# board.net
KiCad netlist of a schematic drawn in EAGLE
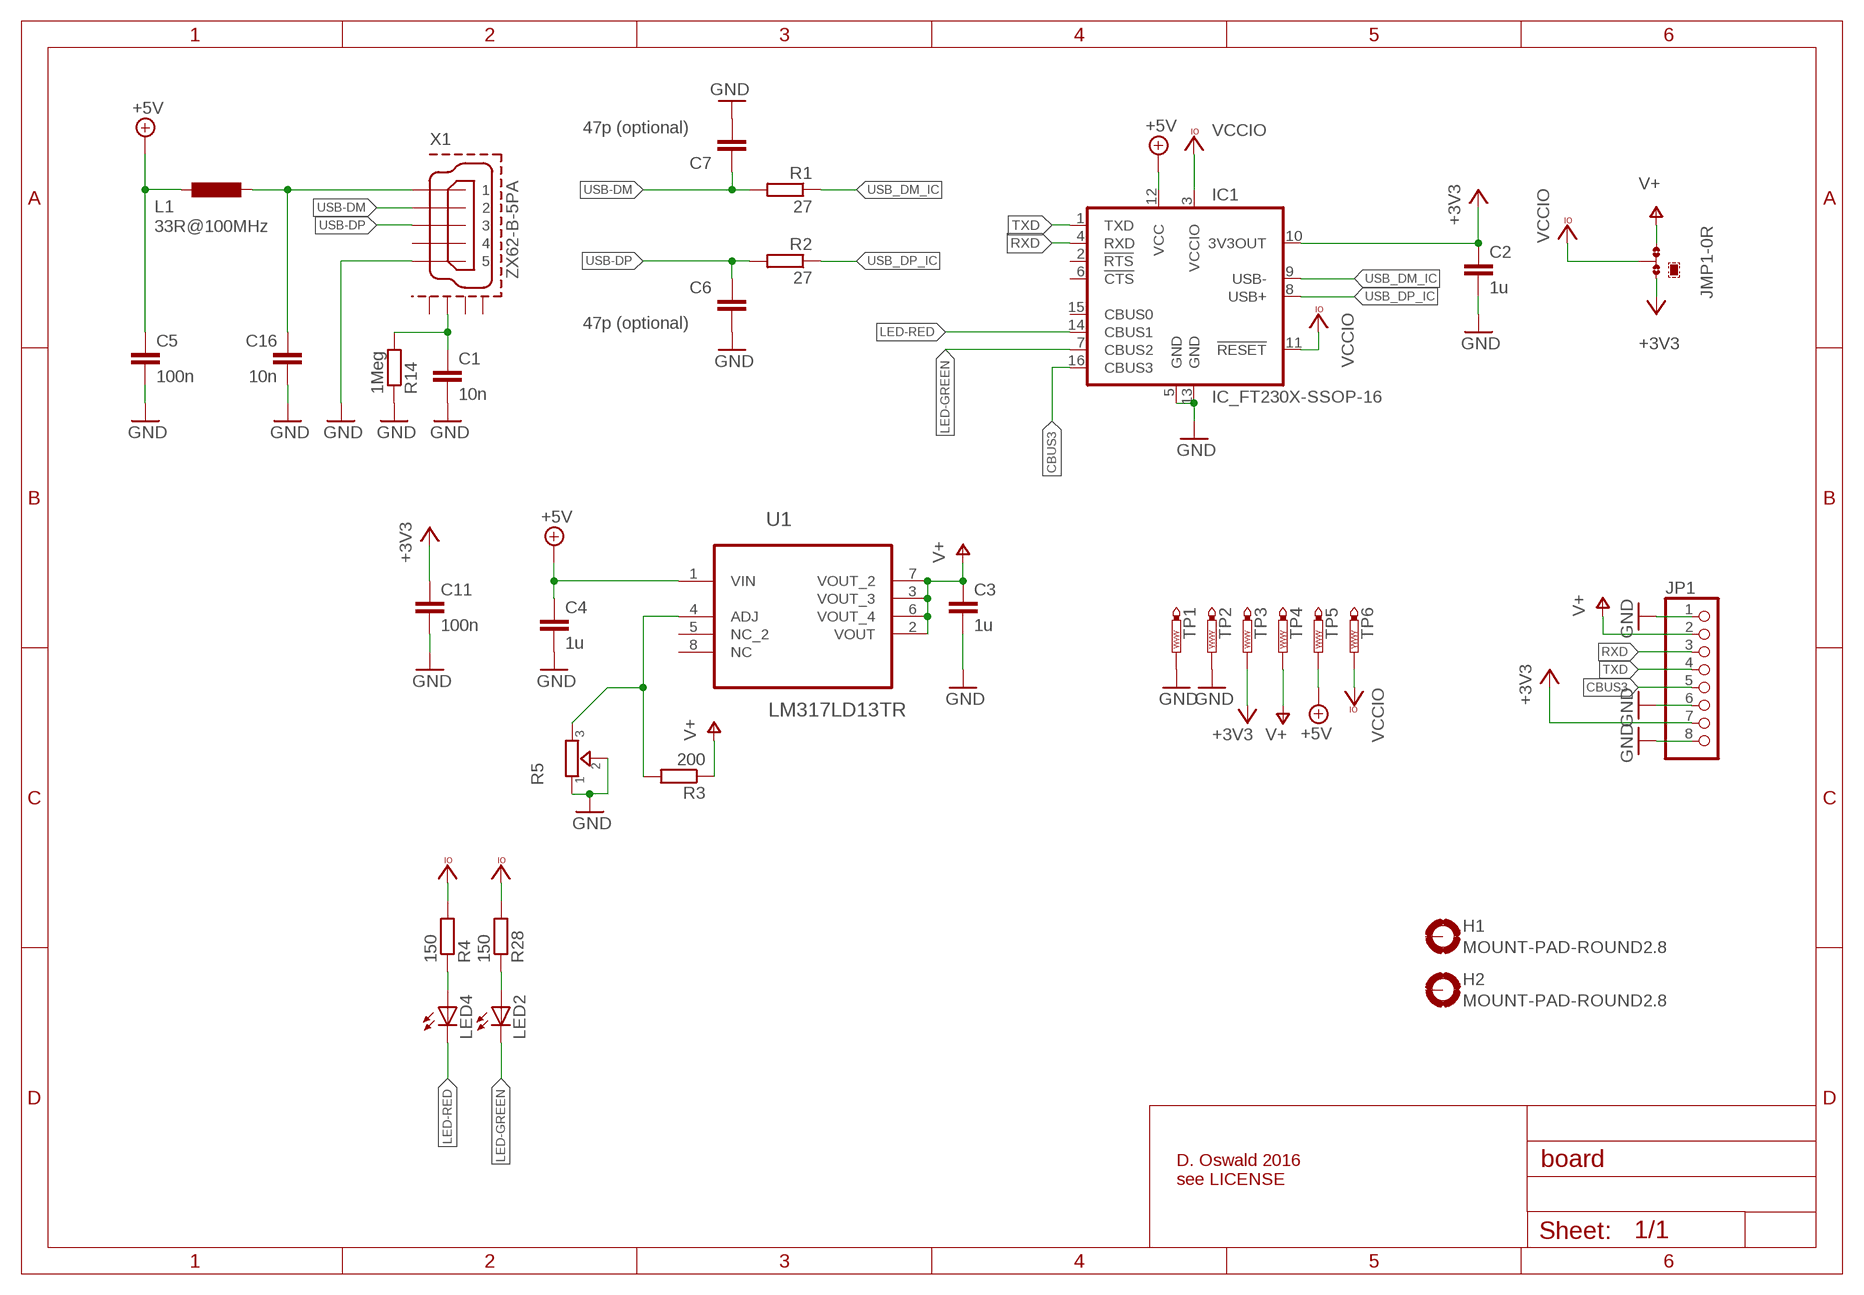
[diagram p0: schematic, sheet 1]

(export (version "E")
  (design (tool "Eeschema 10.0.6"))
  (components
    (comp (ref "C1")
      (value "10n")
      (footprint "eagle-import:C0603K")
      (libsource (lib "eagle-import") (part "C-EUC0603K"))
    )
    (comp (ref "C2")
      (value "1u")
      (footprint "eagle-import:C0805K")
      (libsource (lib "eagle-import") (part "C-EUC0805K"))
    )
    (comp (ref "C3")
      (value "1u")
      (footprint "eagle-import:C0805K")
      (libsource (lib "eagle-import") (part "C-EUC0805K"))
    )
    (comp (ref "C4")
      (value "1u")
      (footprint "eagle-import:C0805K")
      (libsource (lib "eagle-import") (part "C-EUC0805K"))
    )
    (comp (ref "C5")
      (value "100n")
      (footprint "eagle-import:C0603K")
      (libsource (lib "eagle-import") (part "C-EUC0603K"))
    )
    (comp (ref "C6")
      (value "47p (optional)")
      (footprint "eagle-import:C0603K")
      (libsource (lib "eagle-import") (part "C-EUC0603K"))
    )
    (comp (ref "C7")
      (value "47p (optional)")
      (footprint "eagle-import:C0603K")
      (libsource (lib "eagle-import") (part "C-EUC0603K"))
    )
    (comp (ref "C11")
      (value "100n")
      (footprint "eagle-import:C0603K")
      (libsource (lib "eagle-import") (part "C-EUC0603K"))
    )
    (comp (ref "C16")
      (value "10n")
      (footprint "eagle-import:C0603K")
      (libsource (lib "eagle-import") (part "C-EUC0603K"))
    )
    (comp (ref "H1")
      (value "MOUNT-PAD-ROUND2.8")
      (footprint "eagle-import:2,8-PAD")
      (libsource (lib "eagle-import") (part "MOUNT-PAD-ROUND2.8"))
    )
    (comp (ref "H2")
      (value "MOUNT-PAD-ROUND2.8")
      (footprint "eagle-import:2,8-PAD")
      (libsource (lib "eagle-import") (part "MOUNT-PAD-ROUND2.8"))
    )
    (comp (ref "IC1")
      (value "IC_FT230X-SSOP-16")
      (footprint "eagle-import:SSOP-16-FTDI")
      (libsource (lib "eagle-import") (part "IC_FT230X-SSOP-16"))
    )
    (comp (ref "JMP1")
      (value "0R-JUMPA")
      (footprint "eagle-import:A0R-JMP")
      (libsource (lib "eagle-import") (part "0R-JUMPA"))
    )
    (comp (ref "JP1")
      (value "PINHD-1X8/90")
      (footprint "eagle-import:1X08_90")
      (libsource (lib "eagle-import") (part "PINHD-1X8/90"))
    )
    (comp (ref "L1")
      (value "33R@100MHz")
      (footprint "eagle-import:L2012C")
      (libsource (lib "eagle-import") (part "L-EUL2012C"))
    )
    (comp (ref "LED2")
      (value "LEDCHIPLED_0805")
      (footprint "eagle-import:CHIPLED_0805")
      (libsource (lib "eagle-import") (part "LEDCHIPLED_0805"))
    )
    (comp (ref "LED4")
      (value "LEDCHIPLED_0805")
      (footprint "eagle-import:CHIPLED_0805")
      (libsource (lib "eagle-import") (part "LEDCHIPLED_0805"))
    )
    (comp (ref "R1")
      (value "27")
      (footprint "eagle-import:R0603")
      (libsource (lib "eagle-import") (part "R-EU_R0603"))
    )
    (comp (ref "R2")
      (value "27")
      (footprint "eagle-import:R0603")
      (libsource (lib "eagle-import") (part "R-EU_R0603"))
    )
    (comp (ref "R3")
      (value "200")
      (footprint "eagle-import:R0805")
      (libsource (lib "eagle-import") (part "R-EU_R0805"))
    )
    (comp (ref "R4")
      (value "150")
      (footprint "eagle-import:R0603")
      (libsource (lib "eagle-import") (part "R-EU_R0603"))
    )
    (comp (ref "R5")
      (value "TRIMMER-3314G")
      (footprint "eagle-import:TRIMMER_3314G")
      (libsource (lib "eagle-import") (part "TRIMMER-3314G"))
    )
    (comp (ref "R14")
      (value "1Meg")
      (footprint "eagle-import:R0603")
      (libsource (lib "eagle-import") (part "R-EU_R0603"))
    )
    (comp (ref "R28")
      (value "150")
      (footprint "eagle-import:R0603")
      (libsource (lib "eagle-import") (part "R-EU_R0603"))
    )
    (comp (ref "TP1")
      (value "PTR1B1,27")
      (footprint "eagle-import:B1,27")
      (libsource (lib "eagle-import") (part "PTR1B1,27"))
    )
    (comp (ref "TP2")
      (value "PTR1B1,27")
      (footprint "eagle-import:B1,27")
      (libsource (lib "eagle-import") (part "PTR1B1,27"))
    )
    (comp (ref "TP3")
      (value "PTR1B1,27")
      (footprint "eagle-import:B1,27")
      (libsource (lib "eagle-import") (part "PTR1B1,27"))
    )
    (comp (ref "TP4")
      (value "PTR1B1,27")
      (footprint "eagle-import:B1,27")
      (libsource (lib "eagle-import") (part "PTR1B1,27"))
    )
    (comp (ref "TP5")
      (value "PTR1B1,27")
      (footprint "eagle-import:B1,27")
      (libsource (lib "eagle-import") (part "PTR1B1,27"))
    )
    (comp (ref "TP6")
      (value "PTR1B1,27")
      (footprint "eagle-import:B1,27")
      (libsource (lib "eagle-import") (part "PTR1B1,27"))
    )
    (comp (ref "U1")
      (value "LM317LD13TR")
      (footprint "eagle-import:SOIC127P600X175-8N")
      (libsource (lib "eagle-import") (part "LM317LD13TR"))
    )
    (comp (ref "X1")
      (value "ZX62-B-5PA")
      (footprint "eagle-import:ZX62-B-5PA-LONG")
      (libsource (lib "eagle-import") (part "ZX62-B-5PA-LONG"))
    )
  )
  (nets
    (net (code "1") (name "+3V3") (class "Default")
      (node (ref "C11") (pin "1") (pinfunction "1_1") (pintype "passive"))
      (node (ref "C2") (pin "1") (pinfunction "1_1") (pintype "passive"))
      (node (ref "IC1") (pin "10") (pinfunction "3V3OUT_10") (pintype "power_in"))
      (node (ref "JMP1") (pin "1") (pinfunction "1_1") (pintype "passive"))
      (node (ref "JP1") (pin "7") (pinfunction "7_7") (pintype "passive"))
      (node (ref "TP3") (pin "TP") (pinfunction "TP_TP") (pintype "input"))
    )
    (net (code "2") (name "+5V") (class "Default")
      (node (ref "C4") (pin "1") (pinfunction "1_1") (pintype "passive"))
      (node (ref "C5") (pin "1") (pinfunction "1_1") (pintype "passive"))
      (node (ref "IC1") (pin "12") (pinfunction "VCC_12") (pintype "power_in"))
      (node (ref "L1") (pin "2") (pinfunction "2_2") (pintype "passive"))
      (node (ref "TP5") (pin "TP") (pinfunction "TP_TP") (pintype "input"))
      (node (ref "U1") (pin "1") (pinfunction "VIN_1") (pintype "input"))
    )
    (net (code "3") (name "CBUS3") (class "Default")
      (node (ref "IC1") (pin "16") (pinfunction "CBUS3_16") (pintype "bidirectional"))
      (node (ref "JP1") (pin "5") (pinfunction "5_5") (pintype "passive"))
    )
    (net (code "4") (name "GND") (class "Default")
      (node (ref "C1") (pin "2") (pinfunction "2_2") (pintype "passive"))
      (node (ref "C11") (pin "2") (pinfunction "2_2") (pintype "passive"))
      (node (ref "C16") (pin "2") (pinfunction "2_2") (pintype "passive"))
      (node (ref "C2") (pin "2") (pinfunction "2_2") (pintype "passive"))
      (node (ref "C3") (pin "2") (pinfunction "2_2") (pintype "passive"))
      (node (ref "C4") (pin "2") (pinfunction "2_2") (pintype "passive"))
      (node (ref "C5") (pin "2") (pinfunction "2_2") (pintype "passive"))
      (node (ref "C6") (pin "2") (pinfunction "2_2") (pintype "passive"))
      (node (ref "C7") (pin "1") (pinfunction "1_1") (pintype "passive"))
      (node (ref "IC1") (pin "13") (pinfunction "GND_13") (pintype "power_in"))
      (node (ref "IC1") (pin "5") (pinfunction "GND_5") (pintype "power_in"))
      (node (ref "JP1") (pin "1") (pinfunction "1_1") (pintype "passive"))
      (node (ref "JP1") (pin "6") (pinfunction "6_6") (pintype "passive"))
      (node (ref "JP1") (pin "8") (pinfunction "8_8") (pintype "passive"))
      (node (ref "R14") (pin "1") (pinfunction "1_1") (pintype "passive"))
      (node (ref "R5") (pin "1") (pinfunction "1_1") (pintype "passive"))
      (node (ref "R5") (pin "2") (pinfunction "2_2") (pintype "passive"))
      (node (ref "TP1") (pin "TP") (pinfunction "TP_TP") (pintype "input"))
      (node (ref "TP2") (pin "TP") (pinfunction "TP_TP") (pintype "input"))
      (node (ref "X1") (pin "5") (pinfunction "5_5") (pintype "input"))
    )
    (net (code "5") (name "LED-GREEN") (class "Default")
      (node (ref "IC1") (pin "7") (pinfunction "CBUS2_7") (pintype "bidirectional"))
      (node (ref "LED2") (pin "C") (pinfunction "C_C") (pintype "passive"))
    )
    (net (code "6") (name "LED-RED") (class "Default")
      (node (ref "IC1") (pin "14") (pinfunction "CBUS1_14") (pintype "bidirectional"))
      (node (ref "LED4") (pin "C") (pinfunction "C_C") (pintype "passive"))
    )
    (net (code "7") (name "Net-(C16-Pad1)") (class "Default")
      (node (ref "C16") (pin "1") (pinfunction "1_1") (pintype "passive"))
      (node (ref "L1") (pin "1") (pinfunction "1_1") (pintype "passive"))
      (node (ref "X1") (pin "1") (pinfunction "1_1") (pintype "input"))
    )
    (net (code "8") (name "Net-(LED2-PadA)") (class "Default")
      (node (ref "LED2") (pin "A") (pinfunction "A_A") (pintype "passive"))
      (node (ref "R28") (pin "1") (pinfunction "1_1") (pintype "passive"))
    )
    (net (code "9") (name "Net-(LED4-PadA)") (class "Default")
      (node (ref "LED4") (pin "A") (pinfunction "A_A") (pintype "passive"))
      (node (ref "R4") (pin "1") (pinfunction "1_1") (pintype "passive"))
    )
    (net (code "10") (name "Net-(U1-ADJ)") (class "Default")
      (node (ref "R3") (pin "2") (pinfunction "2_2") (pintype "passive"))
      (node (ref "R5") (pin "3") (pinfunction "3_3") (pintype "passive"))
      (node (ref "U1") (pin "4") (pinfunction "ADJ_4") (pintype "input"))
    )
    (net (code "11") (name "Net-(X1-GND2)") (class "Default")
      (node (ref "C1") (pin "1") (pinfunction "1_1") (pintype "passive"))
      (node (ref "R14") (pin "2") (pinfunction "2_2") (pintype "passive"))
      (node (ref "X1") (pin "P$2") (pinfunction "GND2_P$2") (pintype "bidirectional"))
    )
    (net (code "12") (name "RXD") (class "Default")
      (node (ref "IC1") (pin "4") (pinfunction "RXD_4") (pintype "input"))
      (node (ref "JP1") (pin "3") (pinfunction "3_3") (pintype "passive"))
    )
    (net (code "13") (name "TXD") (class "Default")
      (node (ref "IC1") (pin "1") (pinfunction "TXD_1") (pintype "output"))
      (node (ref "JP1") (pin "4") (pinfunction "4_4") (pintype "passive"))
    )
    (net (code "14") (name "USB-DM") (class "Default")
      (node (ref "C7") (pin "2") (pinfunction "2_2") (pintype "passive"))
      (node (ref "R1") (pin "2") (pinfunction "2_2") (pintype "passive"))
      (node (ref "X1") (pin "2") (pinfunction "2_2") (pintype "input"))
    )
    (net (code "15") (name "USB-DP") (class "Default")
      (node (ref "C6") (pin "1") (pinfunction "1_1") (pintype "passive"))
      (node (ref "R2") (pin "2") (pinfunction "2_2") (pintype "passive"))
      (node (ref "X1") (pin "3") (pinfunction "3_3") (pintype "input"))
    )
    (net (code "16") (name "USB_DM_IC") (class "Default")
      (node (ref "IC1") (pin "9") (pinfunction "USB-_9") (pintype "input"))
      (node (ref "R1") (pin "1") (pinfunction "1_1") (pintype "passive"))
    )
    (net (code "17") (name "USB_DP_IC") (class "Default")
      (node (ref "IC1") (pin "8") (pinfunction "USB+_8") (pintype "output"))
      (node (ref "R2") (pin "1") (pinfunction "1_1") (pintype "passive"))
    )
    (net (code "18") (name "V+") (class "Default")
      (node (ref "C3") (pin "1") (pinfunction "1_1") (pintype "passive"))
      (node (ref "JMP1") (pin "3") (pinfunction "3_3") (pintype "passive"))
      (node (ref "JP1") (pin "2") (pinfunction "2_2") (pintype "passive"))
      (node (ref "R3") (pin "1") (pinfunction "1_1") (pintype "passive"))
      (node (ref "TP4") (pin "TP") (pinfunction "TP_TP") (pintype "input"))
      (node (ref "U1") (pin "2") (pinfunction "VOUT_2") (pintype "output"))
      (node (ref "U1") (pin "3") (pinfunction "VOUT_3_3") (pintype "output"))
      (node (ref "U1") (pin "6") (pinfunction "VOUT_4_6") (pintype "output"))
      (node (ref "U1") (pin "7") (pinfunction "VOUT_2_7") (pintype "output"))
    )
    (net (code "19") (name "VCCIO") (class "Default")
      (node (ref "IC1") (pin "11") (pinfunction "~{RESET}_11") (pintype "bidirectional"))
      (node (ref "IC1") (pin "3") (pinfunction "VCCIO_3") (pintype "power_in"))
      (node (ref "JMP1") (pin "2") (pinfunction "2_2") (pintype "passive"))
      (node (ref "R28") (pin "2") (pinfunction "2_2") (pintype "passive"))
      (node (ref "R4") (pin "2") (pinfunction "2_2") (pintype "passive"))
      (node (ref "TP6") (pin "TP") (pinfunction "TP_TP") (pintype "input"))
    )
    (net (code "20") (name "unconnected-(H1-MOUNT-PadB2,8)") (class "Default")
      (node (ref "H1") (pin "B2,8") (pinfunction "MOUNT_B2,8") (pintype "passive"))
    )
    (net (code "21") (name "unconnected-(H2-MOUNT-PadB2,8)") (class "Default")
      (node (ref "H2") (pin "B2,8") (pinfunction "MOUNT_B2,8") (pintype "passive"))
    )
    (net (code "22") (name "unconnected-(IC1-CBUS0-Pad15)") (class "Default")
      (node (ref "IC1") (pin "15") (pinfunction "CBUS0_15") (pintype "bidirectional"))
    )
    (net (code "23") (name "unconnected-(IC1-~{CTS}-Pad6)") (class "Default")
      (node (ref "IC1") (pin "6") (pinfunction "~{CTS}_6") (pintype "bidirectional"))
    )
    (net (code "24") (name "unconnected-(IC1-~{RTS}-Pad2)") (class "Default")
      (node (ref "IC1") (pin "2") (pinfunction "~{RTS}_2") (pintype "bidirectional"))
    )
    (net (code "25") (name "unconnected-(U1-NC-Pad8)") (class "Default")
      (node (ref "U1") (pin "8") (pinfunction "NC_8") (pintype "no_connect"))
    )
    (net (code "26") (name "unconnected-(U1-NC_2-Pad5)") (class "Default")
      (node (ref "U1") (pin "5") (pinfunction "NC_2_5") (pintype "no_connect"))
    )
    (net (code "27") (name "unconnected-(X1-GND1-PadP$1)") (class "Default")
      (node (ref "X1") (pin "P$1") (pinfunction "GND1_P$1") (pintype "bidirectional"))
    )
    (net (code "28") (name "unconnected-(X1-GND3-PadP$6)") (class "Default")
      (node (ref "X1") (pin "P$6") (pinfunction "GND3_P$6") (pintype "bidirectional"))
    )
    (net (code "29") (name "unconnected-(X1-GND4-PadP$5)") (class "Default")
      (node (ref "X1") (pin "P$5") (pinfunction "GND4_P$5") (pintype "bidirectional"))
    )
    (net (code "30") (name "unconnected-(X1-Pad4)") (class "Default")
      (node (ref "X1") (pin "4") (pinfunction "4_4") (pintype "input"))
    )
  )
)
